# Sheet1.net
KiCad netlist of a schematic drawn in Altium Designer
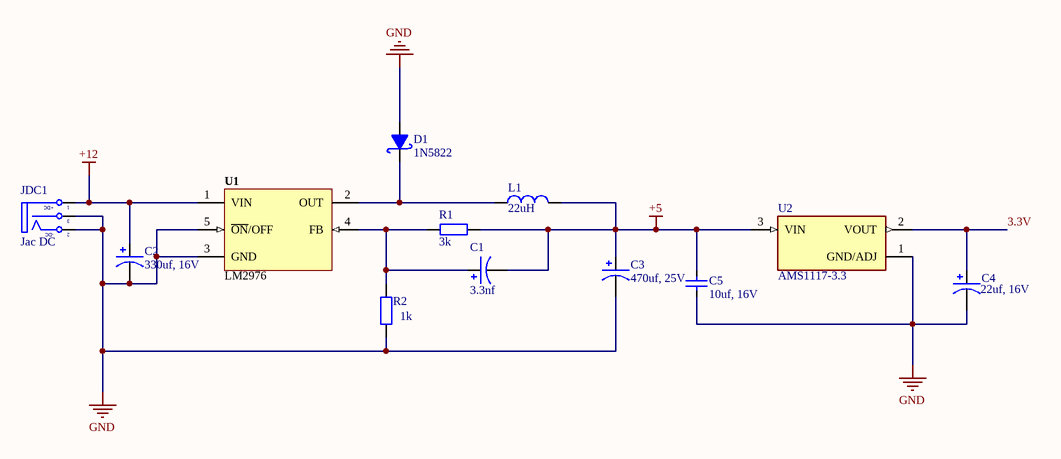
[diagram p0: Sheet1.SchDoc]

(export (version "E")
  (design (tool "Eeschema 10.0.6"))
  (components
    (comp (ref "C1")
      (value "3.3nf")
      (footprint "C3MM")
      (description "Polarized Capacitor (Axial)")
      (fields (field (name "PUBLISHER") "Altium Limited"))
      (libsource (lib "My Library") (part "Cap Pol"))
    )
    (comp (ref "C2")
      (value "330uf, 16V")
      (footprint "C8mm")
      (description "Polarized Capacitor (Axial)")
      (fields (field (name "PUBLISHER") "Altium Limited"))
      (libsource (lib "My Library") (part "Cap Pol"))
    )
    (comp (ref "C3")
      (value "470uf, 25V")
      (footprint "C8mm")
      (description "Polarized Capacitor (Axial)")
      (fields (field (name "PUBLISHER") "Altium Limited"))
      (libsource (lib "My Library") (part "Cap Pol"))
    )
    (comp (ref "C4")
      (value "22uf, 16V")
      (footprint "CA-ALU-4")
      (description "Polarized Capacitor (Axial)")
      (fields (field (name "PUBLISHER") "Altium Limited"))
      (libsource (lib "My Library") (part "Cap Pol"))
    )
    (comp (ref "C5")
      (value "10uf, 16V")
      (footprint "CAP_0805")
      (description "Capacitor")
      (fields (field (name "PUBLISHER") "Altium Limited"))
      (libsource (lib "My Library") (part "CapSMD"))
    )
    (comp (ref "D1")
      (value "1N5822")
      (footprint "SMA")
      (description "Schottky Rectifiers")
      (libsource (lib "My Library") (part "1N5822"))
    )
    (comp (ref "JDC1")
      (value "Jac DC")
      (footprint "DC-IN")
      (description "Jac DC input")
      (libsource (lib "My Library") (part "DCIN"))
    )
    (comp (ref "L1")
      (value "22uH")
      (footprint "L-SMD-M-7.3x4.5")
      (description "Inductor")
      (libsource (lib "My Library") (part "Inductor"))
    )
    (comp (ref "R1")
      (value "3k")
      (footprint "RES-SMD-0805")
      (description "Resistor SMD")
      (fields
        (field (name "MANUFACTURER") "Generic Components")
        (field (name "PUBLISHER") "Altium Hobart Technology Centre")
      )
      (libsource (lib "My Library") (part "Resistor - SMD"))
    )
    (comp (ref "R2")
      (value "1k")
      (footprint "RES-SMD-0805")
      (description "Resistor SMD")
      (fields
        (field (name "MANUFACTURER") "Generic Components")
        (field (name "PUBLISHER") "Altium Hobart Technology Centre")
      )
      (libsource (lib "My Library") (part "Resistor - SMD"))
    )
    (comp (ref "U1") (value "LM2976") (footprint "TO-263") (libsource (lib "My Library") (part "LM2596")))
    (comp (ref "U2")
      (value "AMS1117-3.3")
      (footprint "SOT229P700X180-4N")
      (description "Sot223/Pkg 1-Amp 3.3-Volt Low Drop Out Voltage Regulatator")
      (fields (field (name "MF") "Advanced Monolithic Systems"))
      (libsource (lib "AMS1117-3.3") (part "AMS1117-3.3"))
    )
  )
  (nets
    (net (code "1") (name "+5") (class "Default")
      (node (ref "C1") (pin "2") (pinfunction "2_2") (pintype "passive"))
      (node (ref "C3") (pin "1") (pinfunction "1_1") (pintype "passive"))
      (node (ref "C5") (pin "2") (pinfunction "2_2") (pintype "passive"))
      (node (ref "L1") (pin "2") (pinfunction "2_2") (pintype "passive"))
      (node (ref "R1") (pin "1") (pinfunction "1_1") (pintype "passive"))
      (node (ref "U2") (pin "3") (pinfunction "VIN_3") (pintype "input"))
    )
    (net (code "2") (name "+12") (class "Default")
      (node (ref "C2") (pin "1") (pinfunction "1_1") (pintype "passive"))
      (node (ref "JDC1") (pin "1") (pinfunction "T_1") (pintype "passive"))
      (node (ref "U1") (pin "1") (pinfunction "VIN_1") (pintype "power_in"))
    )
    (net (code "3") (name "/3.3V") (class "Default")
      (node (ref "C4") (pin "1") (pinfunction "1_1") (pintype "passive"))
      (node (ref "U2") (pin "2") (pinfunction "VOUT_2") (pintype "output"))
    )
    (net (code "4") (name "GND") (class "Default")
      (node (ref "C2") (pin "2") (pinfunction "2_2") (pintype "passive"))
      (node (ref "C3") (pin "2") (pinfunction "2_2") (pintype "passive"))
      (node (ref "C4") (pin "2") (pinfunction "2_2") (pintype "passive"))
      (node (ref "C5") (pin "1") (pinfunction "1_1") (pintype "passive"))
      (node (ref "D1") (pin "1") (pinfunction "A_1") (pintype "passive"))
      (node (ref "JDC1") (pin "2") (pinfunction "TN_2") (pintype "passive"))
      (node (ref "JDC1") (pin "3") (pinfunction "S_3") (pintype "power_in"))
      (node (ref "R2") (pin "1") (pinfunction "1_1") (pintype "passive"))
      (node (ref "U1") (pin "3") (pinfunction "GND_3") (pintype "power_in"))
      (node (ref "U1") (pin "5") (pinfunction "~{ON}/OFF_5") (pintype "input"))
      (node (ref "U2") (pin "1") (pinfunction "GND/ADJ_1") (pintype "power_in"))
    )
    (net (code "5") (name "Net-(D1-K)") (class "Default")
      (node (ref "D1") (pin "2") (pinfunction "K_2") (pintype "passive"))
      (node (ref "L1") (pin "1") (pinfunction "1_1") (pintype "passive"))
      (node (ref "U1") (pin "2") (pinfunction "OUT_2") (pintype "power_in"))
    )
    (net (code "6") (name "Net-(U1-FB)") (class "Default")
      (node (ref "C1") (pin "1") (pinfunction "1_1") (pintype "passive"))
      (node (ref "R1") (pin "2") (pinfunction "2_2") (pintype "passive"))
      (node (ref "R2") (pin "2") (pinfunction "2_2") (pintype "passive"))
      (node (ref "U1") (pin "4") (pinfunction "FB_4") (pintype "input"))
    )
  )
)
